# mini_backplane.net
KiCad netlist of a schematic drawn in Altium Designer
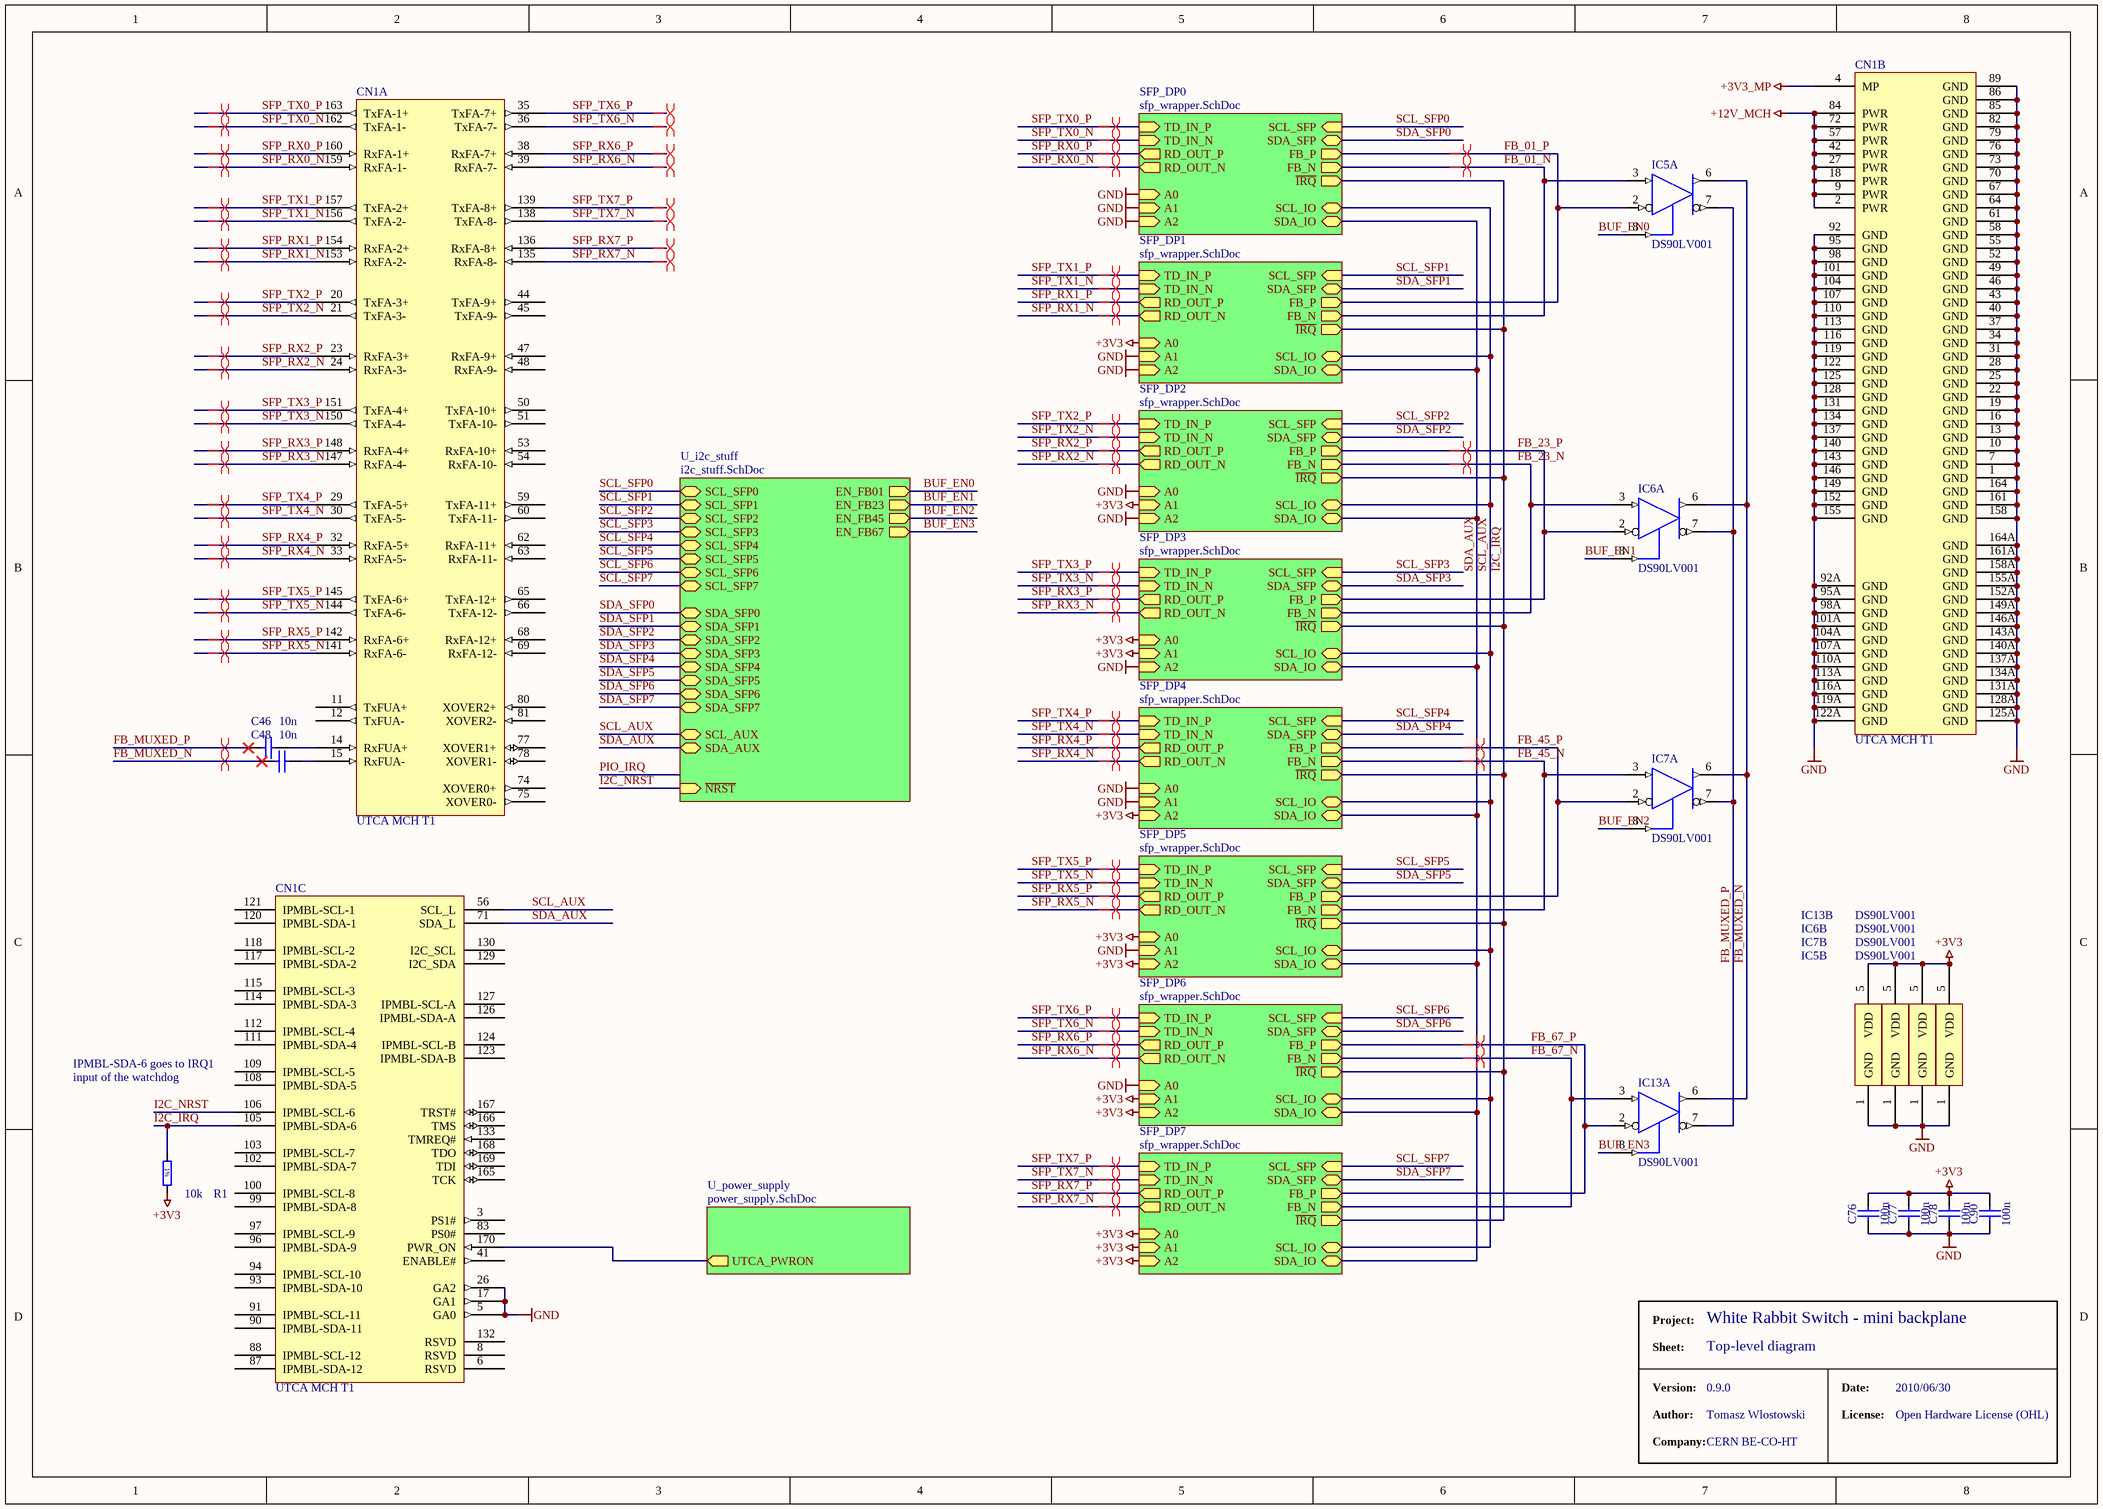
[diagram p0: mini_backplane.SchDoc]

(export (version "E")
  (design (tool "Eeschema 10.0.6"))
  (components
    (comp (ref "C46")
      (value "10n")
      (footprint "CAPC1608X87N")
      (description "Non-polarised capacitor")
      (fields
        (field (name "PART NUMBER") "CC0603_10NF_50V_10%_X7R")
        (field (name "VOLTAGE") "50V")
        (field (name "AUTHOR") "CERN DEM JLC")
      )
      (libsource (lib "Capacitors") (part "Capacitor - non polarized"))
    )
    (comp (ref "C48")
      (value "10n")
      (footprint "CAPC1608X87N")
      (description "Non-polarised capacitor")
      (fields
        (field (name "PART NUMBER") "CC0603_10NF_50V_10%_X7R")
        (field (name "VOLTAGE") "50V")
        (field (name "AUTHOR") "CERN DEM JLC")
      )
      (libsource (lib "Capacitors") (part "Capacitor - non polarized"))
    )
    (comp (ref "C76")
      (value "100n")
      (footprint "CAPC1608X87N")
      (description "Non-polarised capacitor")
      (fields
        (field (name "PART NUMBER") "CC0603_100NF_50V_10%_X7R")
        (field (name "VOLTAGE") "50V")
        (field (name "AUTHOR") "CERN DEM JLC")
      )
      (libsource (lib "Capacitors") (part "Capacitor - non polarized"))
    )
    (comp (ref "C77")
      (value "100n")
      (footprint "CAPC1608X87N")
      (description "Non-polarised capacitor")
      (fields
        (field (name "PART NUMBER") "CC0603_100NF_50V_10%_X7R")
        (field (name "VOLTAGE") "50V")
        (field (name "AUTHOR") "CERN DEM JLC")
      )
      (libsource (lib "Capacitors") (part "Capacitor - non polarized"))
    )
    (comp (ref "C78")
      (value "100n")
      (footprint "CAPC1608X87N")
      (description "Non-polarised capacitor")
      (fields
        (field (name "PART NUMBER") "CC0603_100NF_50V_10%_X7R")
        (field (name "VOLTAGE") "50V")
        (field (name "AUTHOR") "CERN DEM JLC")
      )
      (libsource (lib "Capacitors") (part "Capacitor - non polarized"))
    )
    (comp (ref "C90")
      (value "100n")
      (footprint "CAPC1608X87N")
      (description "Non-polarised capacitor")
      (fields
        (field (name "PART NUMBER") "CC0603_100NF_50V_10%_X7R")
        (field (name "VOLTAGE") "50V")
        (field (name "AUTHOR") "CERN DEM JLC")
      )
      (libsource (lib "Capacitors") (part "Capacitor - non polarized"))
    )
    (comp (ref "CN1")
      (value "UTCA MCH T1")
      (footprint "CON_AMC_MOLEX_75800_00001_REVERSE")
      (description "microTCA MTCA.0  MCH socket (AMC0.0 B+ connector with reversed pins)")
      (libsource (lib "wr_switch") (part "UTCA_MCH_SOCKET"))
    )
    (comp (ref "IC5")
      (value "DS90LV001")
      (footprint "SOIC127P600-8AL")
      (description "LVDS buffer with enable")
      (libsource (lib "wr_switch") (part "DS90LV001"))
    )
    (comp (ref "IC6")
      (value "DS90LV001")
      (footprint "SOIC127P600-8AL")
      (description "LVDS buffer with enable")
      (libsource (lib "wr_switch") (part "DS90LV001"))
    )
    (comp (ref "IC7")
      (value "DS90LV001")
      (footprint "SOIC127P600-8AL")
      (description "LVDS buffer with enable")
      (libsource (lib "wr_switch") (part "DS90LV001"))
    )
    (comp (ref "IC13")
      (value "DS90LV001")
      (footprint "SOIC127P600-8AL")
      (description "LVDS buffer with enable")
      (libsource (lib "wr_switch") (part "DS90LV001"))
    )
    (comp (ref "R1")
      (value "10k")
      (footprint "RESC1608X55N")
      (description "Resistor - 1%")
      (fields
        (field (name "PART NUMBER") "R0603_10K_1%_0.1W_100PPM")
        (field (name "POWER") "0.1W")
        (field (name "AUTHOR") "CERN DEM JLC")
      )
      (libsource (lib "Resistors") (part "Resistor - 1%"))
    )
  )
  (nets
    (net (code "1") (name "+3V3") (class "Default")
      (node (ref "C76") (pin "2") (pinfunction "2_2") (pintype "passive"))
      (node (ref "C77") (pin "2") (pinfunction "2_2") (pintype "passive"))
      (node (ref "C78") (pin "2") (pinfunction "2_2") (pintype "passive"))
      (node (ref "C90") (pin "2") (pinfunction "2_2") (pintype "passive"))
      (node (ref "IC13") (pin "5") (pinfunction "VDD_5") (pintype "power_in"))
      (node (ref "IC5") (pin "5") (pinfunction "VDD_5") (pintype "power_in"))
      (node (ref "IC6") (pin "5") (pinfunction "VDD_5") (pintype "power_in"))
      (node (ref "IC7") (pin "5") (pinfunction "VDD_5") (pintype "power_in"))
      (node (ref "R1") (pin "2") (pinfunction "2_2") (pintype "passive"))
    )
    (net (code "2") (name "+3V3_MP") (class "Default")
      (node (ref "CN1") (pin "4") (pinfunction "MP_4") (pintype "power_in"))
    )
    (net (code "3") (name "+12V_MCH") (class "Default")
      (node (ref "CN1") (pin "18") (pinfunction "PWR_18") (pintype "power_in"))
      (node (ref "CN1") (pin "2") (pinfunction "PWR_2") (pintype "power_in"))
      (node (ref "CN1") (pin "27") (pinfunction "PWR_27") (pintype "power_in"))
      (node (ref "CN1") (pin "42") (pinfunction "PWR_42") (pintype "power_in"))
      (node (ref "CN1") (pin "57") (pinfunction "PWR_57") (pintype "power_in"))
      (node (ref "CN1") (pin "72") (pinfunction "PWR_72") (pintype "power_in"))
      (node (ref "CN1") (pin "84") (pinfunction "PWR_84") (pintype "power_in"))
      (node (ref "CN1") (pin "9") (pinfunction "PWR_9") (pintype "power_in"))
    )
    (net (code "4") (name "/BUF_EN0") (class "Default")
      (node (ref "IC5") (pin "8") (pinfunction "EN_8") (pintype "input"))
    )
    (net (code "5") (name "/BUF_EN1") (class "Default")
      (node (ref "IC6") (pin "8") (pinfunction "EN_8") (pintype "input"))
    )
    (net (code "6") (name "/BUF_EN2") (class "Default")
      (node (ref "IC7") (pin "8") (pinfunction "EN_8") (pintype "input"))
    )
    (net (code "7") (name "/BUF_EN3") (class "Default")
      (node (ref "IC13") (pin "8") (pinfunction "EN_8") (pintype "input"))
    )
    (net (code "8") (name "/FB_01_N") (class "Default")
      (node (ref "IC5") (pin "3") (pinfunction "IN+_3") (pintype "input"))
    )
    (net (code "9") (name "/FB_01_P") (class "Default")
      (node (ref "IC5") (pin "2") (pinfunction "IN-_2") (pintype "input"))
    )
    (net (code "10") (name "/FB_23_N") (class "Default")
      (node (ref "IC6") (pin "3") (pinfunction "IN+_3") (pintype "input"))
    )
    (net (code "11") (name "/FB_23_P") (class "Default")
      (node (ref "IC6") (pin "2") (pinfunction "IN-_2") (pintype "input"))
    )
    (net (code "12") (name "/FB_45_N") (class "Default")
      (node (ref "IC7") (pin "3") (pinfunction "IN+_3") (pintype "input"))
    )
    (net (code "13") (name "/FB_45_P") (class "Default")
      (node (ref "IC7") (pin "2") (pinfunction "IN-_2") (pintype "input"))
    )
    (net (code "14") (name "/FB_67_N") (class "Default")
      (node (ref "IC13") (pin "3") (pinfunction "IN+_3") (pintype "input"))
    )
    (net (code "15") (name "/FB_67_P") (class "Default")
      (node (ref "IC13") (pin "2") (pinfunction "IN-_2") (pintype "input"))
    )
    (net (code "16") (name "/FB_MUXED_N") (class "Default")
      (node (ref "C48") (pin "1") (pinfunction "1_1") (pintype "passive"))
      (node (ref "IC13") (pin "6") (pinfunction "OUT+_6") (pintype "output"))
      (node (ref "IC5") (pin "6") (pinfunction "OUT+_6") (pintype "output"))
      (node (ref "IC6") (pin "6") (pinfunction "OUT+_6") (pintype "output"))
      (node (ref "IC7") (pin "6") (pinfunction "OUT+_6") (pintype "output"))
    )
    (net (code "17") (name "/FB_MUXED_P") (class "Default")
      (node (ref "C46") (pin "1") (pinfunction "1_1") (pintype "passive"))
      (node (ref "IC13") (pin "7") (pinfunction "OUT-_7") (pintype "output"))
      (node (ref "IC5") (pin "7") (pinfunction "OUT-_7") (pintype "output"))
      (node (ref "IC6") (pin "7") (pinfunction "OUT-_7") (pintype "output"))
      (node (ref "IC7") (pin "7") (pinfunction "OUT-_7") (pintype "output"))
    )
    (net (code "18") (name "/I2C_IRQ") (class "Default")
      (node (ref "CN1") (pin "105") (pinfunction "IPMBL-SDA-6_105") (pintype "open_collector"))
      (node (ref "R1") (pin "1") (pinfunction "1_1") (pintype "passive"))
    )
    (net (code "19") (name "/I2C_NRST") (class "Default")
      (node (ref "CN1") (pin "106") (pinfunction "IPMBL-SCL-6_106") (pintype "open_collector"))
    )
    (net (code "21") (name "/SCL_AUX") (class "Default")
      (node (ref "CN1") (pin "56") (pinfunction "SCL_L_56") (pintype "open_collector"))
    )
    (net (code "30") (name "/SDA_AUX") (class "Default")
      (node (ref "CN1") (pin "71") (pinfunction "SDA_L_71") (pintype "open_collector"))
    )
    (net (code "39") (name "/SFP_RX0_N") (class "Default")
      (node (ref "CN1") (pin "159") (pinfunction "RxFA-1-_159") (pintype "input"))
    )
    (net (code "40") (name "/SFP_RX0_P") (class "Default")
      (node (ref "CN1") (pin "160") (pinfunction "RxFA-1+_160") (pintype "input"))
    )
    (net (code "41") (name "/SFP_RX1_N") (class "Default")
      (node (ref "CN1") (pin "153") (pinfunction "RxFA-2-_153") (pintype "input"))
    )
    (net (code "42") (name "/SFP_RX1_P") (class "Default")
      (node (ref "CN1") (pin "154") (pinfunction "RxFA-2+_154") (pintype "input"))
    )
    (net (code "43") (name "/SFP_RX2_N") (class "Default")
      (node (ref "CN1") (pin "24") (pinfunction "RxFA-3-_24") (pintype "input"))
    )
    (net (code "44") (name "/SFP_RX2_P") (class "Default")
      (node (ref "CN1") (pin "23") (pinfunction "RxFA-3+_23") (pintype "input"))
    )
    (net (code "45") (name "/SFP_RX3_N") (class "Default")
      (node (ref "CN1") (pin "147") (pinfunction "RxFA-4-_147") (pintype "input"))
    )
    (net (code "46") (name "/SFP_RX3_P") (class "Default")
      (node (ref "CN1") (pin "148") (pinfunction "RxFA-4+_148") (pintype "input"))
    )
    (net (code "47") (name "/SFP_RX4_N") (class "Default")
      (node (ref "CN1") (pin "33") (pinfunction "RxFA-5-_33") (pintype "input"))
    )
    (net (code "48") (name "/SFP_RX4_P") (class "Default")
      (node (ref "CN1") (pin "32") (pinfunction "RxFA-5+_32") (pintype "input"))
    )
    (net (code "49") (name "/SFP_RX5_N") (class "Default")
      (node (ref "CN1") (pin "141") (pinfunction "RxFA-6-_141") (pintype "input"))
    )
    (net (code "50") (name "/SFP_RX5_P") (class "Default")
      (node (ref "CN1") (pin "142") (pinfunction "RxFA-6+_142") (pintype "input"))
    )
    (net (code "51") (name "/SFP_RX6_N") (class "Default")
      (node (ref "CN1") (pin "39") (pinfunction "RxFA-7-_39") (pintype "input"))
    )
    (net (code "52") (name "/SFP_RX6_P") (class "Default")
      (node (ref "CN1") (pin "38") (pinfunction "RxFA-7+_38") (pintype "input"))
    )
    (net (code "53") (name "/SFP_RX7_N") (class "Default")
      (node (ref "CN1") (pin "135") (pinfunction "RxFA-8-_135") (pintype "input"))
    )
    (net (code "54") (name "/SFP_RX7_P") (class "Default")
      (node (ref "CN1") (pin "136") (pinfunction "RxFA-8+_136") (pintype "input"))
    )
    (net (code "55") (name "/SFP_TX0_N") (class "Default")
      (node (ref "CN1") (pin "162") (pinfunction "TxFA-1-_162") (pintype "output"))
    )
    (net (code "56") (name "/SFP_TX0_P") (class "Default")
      (node (ref "CN1") (pin "163") (pinfunction "TxFA-1+_163") (pintype "output"))
    )
    (net (code "57") (name "/SFP_TX1_N") (class "Default")
      (node (ref "CN1") (pin "156") (pinfunction "TxFA-2-_156") (pintype "output"))
    )
    (net (code "58") (name "/SFP_TX1_P") (class "Default")
      (node (ref "CN1") (pin "157") (pinfunction "TxFA-2+_157") (pintype "output"))
    )
    (net (code "59") (name "/SFP_TX2_N") (class "Default")
      (node (ref "CN1") (pin "21") (pinfunction "TxFA-3-_21") (pintype "output"))
    )
    (net (code "60") (name "/SFP_TX2_P") (class "Default")
      (node (ref "CN1") (pin "20") (pinfunction "TxFA-3+_20") (pintype "output"))
    )
    (net (code "61") (name "/SFP_TX3_N") (class "Default")
      (node (ref "CN1") (pin "150") (pinfunction "TxFA-4-_150") (pintype "output"))
    )
    (net (code "62") (name "/SFP_TX3_P") (class "Default")
      (node (ref "CN1") (pin "151") (pinfunction "TxFA-4+_151") (pintype "output"))
    )
    (net (code "63") (name "/SFP_TX4_N") (class "Default")
      (node (ref "CN1") (pin "30") (pinfunction "TxFA-5-_30") (pintype "output"))
    )
    (net (code "64") (name "/SFP_TX4_P") (class "Default")
      (node (ref "CN1") (pin "29") (pinfunction "TxFA-5+_29") (pintype "output"))
    )
    (net (code "65") (name "/SFP_TX5_N") (class "Default")
      (node (ref "CN1") (pin "144") (pinfunction "TxFA-6-_144") (pintype "output"))
    )
    (net (code "66") (name "/SFP_TX5_P") (class "Default")
      (node (ref "CN1") (pin "145") (pinfunction "TxFA-6+_145") (pintype "output"))
    )
    (net (code "67") (name "/SFP_TX6_N") (class "Default")
      (node (ref "CN1") (pin "36") (pinfunction "TxFA-7-_36") (pintype "output"))
    )
    (net (code "68") (name "/SFP_TX6_P") (class "Default")
      (node (ref "CN1") (pin "35") (pinfunction "TxFA-7+_35") (pintype "output"))
    )
    (net (code "69") (name "/SFP_TX7_N") (class "Default")
      (node (ref "CN1") (pin "138") (pinfunction "TxFA-8-_138") (pintype "output"))
    )
    (net (code "70") (name "/SFP_TX7_P") (class "Default")
      (node (ref "CN1") (pin "139") (pinfunction "TxFA-8+_139") (pintype "output"))
    )
    (net (code "71") (name "/UTCA_PWRON") (class "Default")
      (node (ref "CN1") (pin "170") (pinfunction "PWR_ON_170") (pintype "input"))
    )
    (net (code "72") (name "GND") (class "Default")
      (node (ref "C76") (pin "1") (pinfunction "1_1") (pintype "passive"))
      (node (ref "C77") (pin "1") (pinfunction "1_1") (pintype "passive"))
      (node (ref "C78") (pin "1") (pinfunction "1_1") (pintype "passive"))
      (node (ref "C90") (pin "1") (pinfunction "1_1") (pintype "passive"))
      (node (ref "CN1") (pin "1") (pinfunction "GND_1") (pintype "power_in"))
      (node (ref "CN1") (pin "10") (pinfunction "GND_10") (pintype "power_in"))
      (node (ref "CN1") (pin "101") (pinfunction "GND_101") (pintype "power_in"))
      (node (ref "CN1") (pin "101A") (pinfunction "GND_101A") (pintype "power_in"))
      (node (ref "CN1") (pin "104") (pinfunction "GND_104") (pintype "power_in"))
      (node (ref "CN1") (pin "104A") (pinfunction "GND_104A") (pintype "power_in"))
      (node (ref "CN1") (pin "107") (pinfunction "GND_107") (pintype "power_in"))
      (node (ref "CN1") (pin "107A") (pinfunction "GND_107A") (pintype "power_in"))
      (node (ref "CN1") (pin "110") (pinfunction "GND_110") (pintype "power_in"))
      (node (ref "CN1") (pin "110A") (pinfunction "GND_110A") (pintype "power_in"))
      (node (ref "CN1") (pin "113") (pinfunction "GND_113") (pintype "power_in"))
      (node (ref "CN1") (pin "113A") (pinfunction "GND_113A") (pintype "power_in"))
      (node (ref "CN1") (pin "116") (pinfunction "GND_116") (pintype "power_in"))
      (node (ref "CN1") (pin "116A") (pinfunction "GND_116A") (pintype "power_in"))
      (node (ref "CN1") (pin "119") (pinfunction "GND_119") (pintype "power_in"))
      (node (ref "CN1") (pin "119A") (pinfunction "GND_119A") (pintype "power_in"))
      (node (ref "CN1") (pin "122") (pinfunction "GND_122") (pintype "power_in"))
      (node (ref "CN1") (pin "122A") (pinfunction "GND_122A") (pintype "power_in"))
      (node (ref "CN1") (pin "125") (pinfunction "GND_125") (pintype "power_in"))
      (node (ref "CN1") (pin "125A") (pinfunction "GND_125A") (pintype "power_in"))
      (node (ref "CN1") (pin "128") (pinfunction "GND_128") (pintype "power_in"))
      (node (ref "CN1") (pin "128A") (pinfunction "GND_128A") (pintype "power_in"))
      (node (ref "CN1") (pin "13") (pinfunction "GND_13") (pintype "power_in"))
      (node (ref "CN1") (pin "131") (pinfunction "GND_131") (pintype "power_in"))
      (node (ref "CN1") (pin "131A") (pinfunction "GND_131A") (pintype "power_in"))
      (node (ref "CN1") (pin "134") (pinfunction "GND_134") (pintype "power_in"))
      (node (ref "CN1") (pin "134A") (pinfunction "GND_134A") (pintype "power_in"))
      (node (ref "CN1") (pin "137") (pinfunction "GND_137") (pintype "power_in"))
      (node (ref "CN1") (pin "137A") (pinfunction "GND_137A") (pintype "power_in"))
      (node (ref "CN1") (pin "140") (pinfunction "GND_140") (pintype "power_in"))
      (node (ref "CN1") (pin "140A") (pinfunction "GND_140A") (pintype "power_in"))
      (node (ref "CN1") (pin "143") (pinfunction "GND_143") (pintype "power_in"))
      (node (ref "CN1") (pin "143A") (pinfunction "GND_143A") (pintype "power_in"))
      (node (ref "CN1") (pin "146") (pinfunction "GND_146") (pintype "power_in"))
      (node (ref "CN1") (pin "146A") (pinfunction "GND_146A") (pintype "power_in"))
      (node (ref "CN1") (pin "149") (pinfunction "GND_149") (pintype "power_in"))
      (node (ref "CN1") (pin "149A") (pinfunction "GND_149A") (pintype "power_in"))
      (node (ref "CN1") (pin "152") (pinfunction "GND_152") (pintype "power_in"))
      (node (ref "CN1") (pin "152A") (pinfunction "GND_152A") (pintype "power_in"))
      (node (ref "CN1") (pin "155") (pinfunction "GND_155") (pintype "power_in"))
      (node (ref "CN1") (pin "155A") (pinfunction "GND_155A") (pintype "power_in"))
      (node (ref "CN1") (pin "158") (pinfunction "GND_158") (pintype "power_in"))
      (node (ref "CN1") (pin "158A") (pinfunction "GND_158A") (pintype "power_in"))
      (node (ref "CN1") (pin "16") (pinfunction "GND_16") (pintype "power_in"))
      (node (ref "CN1") (pin "161") (pinfunction "GND_161") (pintype "power_in"))
      (node (ref "CN1") (pin "161A") (pinfunction "GND_161A") (pintype "power_in"))
      (node (ref "CN1") (pin "164") (pinfunction "GND_164") (pintype "power_in"))
      (node (ref "CN1") (pin "164A") (pinfunction "GND_164A") (pintype "power_in"))
      (node (ref "CN1") (pin "17") (pinfunction "GA1_17") (pintype "output"))
      (node (ref "CN1") (pin "19") (pinfunction "GND_19") (pintype "power_in"))
      (node (ref "CN1") (pin "22") (pinfunction "GND_22") (pintype "power_in"))
      (node (ref "CN1") (pin "25") (pinfunction "GND_25") (pintype "power_in"))
      (node (ref "CN1") (pin "26") (pinfunction "GA2_26") (pintype "output"))
      (node (ref "CN1") (pin "28") (pinfunction "GND_28") (pintype "power_in"))
      (node (ref "CN1") (pin "31") (pinfunction "GND_31") (pintype "power_in"))
      (node (ref "CN1") (pin "34") (pinfunction "GND_34") (pintype "power_in"))
      (node (ref "CN1") (pin "37") (pinfunction "GND_37") (pintype "power_in"))
      (node (ref "CN1") (pin "40") (pinfunction "GND_40") (pintype "power_in"))
      (node (ref "CN1") (pin "43") (pinfunction "GND_43") (pintype "power_in"))
      (node (ref "CN1") (pin "46") (pinfunction "GND_46") (pintype "power_in"))
      (node (ref "CN1") (pin "49") (pinfunction "GND_49") (pintype "power_in"))
      (node (ref "CN1") (pin "5") (pinfunction "GA0_5") (pintype "output"))
      (node (ref "CN1") (pin "52") (pinfunction "GND_52") (pintype "power_in"))
      (node (ref "CN1") (pin "55") (pinfunction "GND_55") (pintype "power_in"))
      (node (ref "CN1") (pin "58") (pinfunction "GND_58") (pintype "power_in"))
      (node (ref "CN1") (pin "61") (pinfunction "GND_61") (pintype "power_in"))
      (node (ref "CN1") (pin "64") (pinfunction "GND_64") (pintype "power_in"))
      (node (ref "CN1") (pin "67") (pinfunction "GND_67") (pintype "power_in"))
      (node (ref "CN1") (pin "7") (pinfunction "GND_7") (pintype "power_in"))
      (node (ref "CN1") (pin "70") (pinfunction "GND_70") (pintype "power_in"))
      (node (ref "CN1") (pin "73") (pinfunction "GND_73") (pintype "power_in"))
      (node (ref "CN1") (pin "76") (pinfunction "GND_76") (pintype "power_in"))
      (node (ref "CN1") (pin "79") (pinfunction "GND_79") (pintype "power_in"))
      (node (ref "CN1") (pin "82") (pinfunction "GND_82") (pintype "power_in"))
      (node (ref "CN1") (pin "85") (pinfunction "GND_85") (pintype "power_in"))
      (node (ref "CN1") (pin "86") (pinfunction "GND_86") (pintype "power_in"))
      (node (ref "CN1") (pin "89") (pinfunction "GND_89") (pintype "power_in"))
      (node (ref "CN1") (pin "92") (pinfunction "GND_92") (pintype "power_in"))
      (node (ref "CN1") (pin "92A") (pinfunction "GND_92A") (pintype "power_in"))
      (node (ref "CN1") (pin "95") (pinfunction "GND_95") (pintype "power_in"))
      (node (ref "CN1") (pin "95A") (pinfunction "GND_95A") (pintype "power_in"))
      (node (ref "CN1") (pin "98") (pinfunction "GND_98") (pintype "power_in"))
      (node (ref "CN1") (pin "98A") (pinfunction "GND_98A") (pintype "power_in"))
      (node (ref "IC13") (pin "1") (pinfunction "GND_1") (pintype "power_in"))
      (node (ref "IC5") (pin "1") (pinfunction "GND_1") (pintype "power_in"))
      (node (ref "IC6") (pin "1") (pinfunction "GND_1") (pintype "power_in"))
      (node (ref "IC7") (pin "1") (pinfunction "GND_1") (pintype "power_in"))
    )
    (net (code "73") (name "Net-(CN1A-RxFUA+)") (class "Default")
      (node (ref "C46") (pin "2") (pinfunction "2_2") (pintype "passive"))
      (node (ref "CN1") (pin "14") (pinfunction "RxFUA+_14") (pintype "input"))
    )
    (net (code "74") (name "Net-(CN1A-RxFUA-)") (class "Default")
      (node (ref "C48") (pin "2") (pinfunction "2_2") (pintype "passive"))
      (node (ref "CN1") (pin "15") (pinfunction "RxFUA-_15") (pintype "input"))
    )
    (net (code "75") (name "unconnected-(CN1A-RxFA-9+-Pad47)") (class "Default")
      (node (ref "CN1") (pin "47") (pinfunction "RxFA-9+_47") (pintype "input"))
    )
    (net (code "76") (name "unconnected-(CN1A-RxFA-9--Pad48)") (class "Default")
      (node (ref "CN1") (pin "48") (pinfunction "RxFA-9-_48") (pintype "input"))
    )
    (net (code "77") (name "unconnected-(CN1A-RxFA-10+-Pad53)") (class "Default")
      (node (ref "CN1") (pin "53") (pinfunction "RxFA-10+_53") (pintype "input"))
    )
    (net (code "78") (name "unconnected-(CN1A-RxFA-10--Pad54)") (class "Default")
      (node (ref "CN1") (pin "54") (pinfunction "RxFA-10-_54") (pintype "input"))
    )
    (net (code "79") (name "unconnected-(CN1A-RxFA-11+-Pad62)") (class "Default")
      (node (ref "CN1") (pin "62") (pinfunction "RxFA-11+_62") (pintype "input"))
    )
    (net (code "80") (name "unconnected-(CN1A-RxFA-11--Pad63)") (class "Default")
      (node (ref "CN1") (pin "63") (pinfunction "RxFA-11-_63") (pintype "input"))
    )
    (net (code "81") (name "unconnected-(CN1A-RxFA-12+-Pad68)") (class "Default")
      (node (ref "CN1") (pin "68") (pinfunction "RxFA-12+_68") (pintype "input"))
    )
    (net (code "82") (name "unconnected-(CN1A-RxFA-12--Pad69)") (class "Default")
      (node (ref "CN1") (pin "69") (pinfunction "RxFA-12-_69") (pintype "input"))
    )
    (net (code "83") (name "unconnected-(CN1A-TxFA-9+-Pad44)") (class "Default")
      (node (ref "CN1") (pin "44") (pinfunction "TxFA-9+_44") (pintype "output"))
    )
    (net (code "84") (name "unconnected-(CN1A-TxFA-9--Pad45)") (class "Default")
      (node (ref "CN1") (pin "45") (pinfunction "TxFA-9-_45") (pintype "output"))
    )
    (net (code "85") (name "unconnected-(CN1A-TxFA-10+-Pad50)") (class "Default")
      (node (ref "CN1") (pin "50") (pinfunction "TxFA-10+_50") (pintype "output"))
    )
    (net (code "86") (name "unconnected-(CN1A-TxFA-10--Pad51)") (class "Default")
      (node (ref "CN1") (pin "51") (pinfunction "TxFA-10-_51") (pintype "output"))
    )
    (net (code "87") (name "unconnected-(CN1A-TxFA-11+-Pad59)") (class "Default")
      (node (ref "CN1") (pin "59") (pinfunction "TxFA-11+_59") (pintype "output"))
    )
    (net (code "88") (name "unconnected-(CN1A-TxFA-11--Pad60)") (class "Default")
      (node (ref "CN1") (pin "60") (pinfunction "TxFA-11-_60") (pintype "output"))
    )
    (net (code "89") (name "unconnected-(CN1A-TxFA-12+-Pad65)") (class "Default")
      (node (ref "CN1") (pin "65") (pinfunction "TxFA-12+_65") (pintype "output"))
    )
    (net (code "90") (name "unconnected-(CN1A-TxFA-12--Pad66)") (class "Default")
      (node (ref "CN1") (pin "66") (pinfunction "TxFA-12-_66") (pintype "output"))
    )
    (net (code "91") (name "unconnected-(CN1A-TxFUA+-Pad11)") (class "Default")
      (node (ref "CN1") (pin "11") (pinfunction "TxFUA+_11") (pintype "output"))
    )
    (net (code "92") (name "unconnected-(CN1A-TxFUA--Pad12)") (class "Default")
      (node (ref "CN1") (pin "12") (pinfunction "TxFUA-_12") (pintype "output"))
    )
    (net (code "93") (name "unconnected-(CN1A-XOVER0+-Pad74)") (class "Default")
      (node (ref "CN1") (pin "74") (pinfunction "XOVER0+_74") (pintype "output"))
    )
    (net (code "94") (name "unconnected-(CN1A-XOVER0--Pad75)") (class "Default")
      (node (ref "CN1") (pin "75") (pinfunction "XOVER0-_75") (pintype "output"))
    )
    (net (code "95") (name "unconnected-(CN1A-XOVER1+-Pad77)") (class "Default")
      (node (ref "CN1") (pin "77") (pinfunction "XOVER1+_77") (pintype "bidirectional"))
    )
    (net (code "96") (name "unconnected-(CN1A-XOVER1--Pad78)") (class "Default")
      (node (ref "CN1") (pin "78") (pinfunction "XOVER1-_78") (pintype "bidirectional"))
    )
    (net (code "97") (name "unconnected-(CN1A-XOVER2+-Pad80)") (class "Default")
      (node (ref "CN1") (pin "80") (pinfunction "XOVER2+_80") (pintype "input"))
    )
    (net (code "98") (name "unconnected-(CN1A-XOVER2--Pad81)") (class "Default")
      (node (ref "CN1") (pin "81") (pinfunction "XOVER2-_81") (pintype "input"))
    )
    (net (code "99") (name "unconnected-(CN1C-ENABLE#-Pad41)") (class "Default")
      (node (ref "CN1") (pin "41") (pinfunction "ENABLE#_41") (pintype "output"))
    )
    (net (code "100") (name "unconnected-(CN1C-I2C_SCL-Pad130)") (class "Default")
      (node (ref "CN1") (pin "130") (pinfunction "I2C_SCL_130") (pintype "open_collector"))
    )
    (net (code "101") (name "unconnected-(CN1C-I2C_SDA-Pad129)") (class "Default")
      (node (ref "CN1") (pin "129") (pinfunction "I2C_SDA_129") (pintype "open_collector"))
    )
    (net (code "102") (name "unconnected-(CN1C-IPMBL-SCL-1-Pad121)") (class "Default")
      (node (ref "CN1") (pin "121") (pinfunction "IPMBL-SCL-1_121") (pintype "open_collector"))
    )
    (net (code "103") (name "unconnected-(CN1C-IPMBL-SCL-2-Pad118)") (class "Default")
      (node (ref "CN1") (pin "118") (pinfunction "IPMBL-SCL-2_118") (pintype "open_collector"))
    )
    (net (code "104") (name "unconnected-(CN1C-IPMBL-SCL-3-Pad115)") (class "Default")
      (node (ref "CN1") (pin "115") (pinfunction "IPMBL-SCL-3_115") (pintype "open_collector"))
    )
    (net (code "105") (name "unconnected-(CN1C-IPMBL-SCL-4-Pad112)") (class "Default")
      (node (ref "CN1") (pin "112") (pinfunction "IPMBL-SCL-4_112") (pintype "open_collector"))
    )
    (net (code "106") (name "unconnected-(CN1C-IPMBL-SCL-5-Pad109)") (class "Default")
      (node (ref "CN1") (pin "109") (pinfunction "IPMBL-SCL-5_109") (pintype "open_collector"))
    )
    (net (code "107") (name "unconnected-(CN1C-IPMBL-SCL-7-Pad103)") (class "Default")
      (node (ref "CN1") (pin "103") (pinfunction "IPMBL-SCL-7_103") (pintype "open_collector"))
    )
    (net (code "108") (name "unconnected-(CN1C-IPMBL-SCL-8-Pad100)") (class "Default")
      (node (ref "CN1") (pin "100") (pinfunction "IPMBL-SCL-8_100") (pintype "open_collector"))
    )
    (net (code "109") (name "unconnected-(CN1C-IPMBL-SCL-9-Pad97)") (class "Default")
      (node (ref "CN1") (pin "97") (pinfunction "IPMBL-SCL-9_97") (pintype "open_collector"))
    )
    (net (code "110") (name "unconnected-(CN1C-IPMBL-SCL-10-Pad94)") (class "Default")
      (node (ref "CN1") (pin "94") (pinfunction "IPMBL-SCL-10_94") (pintype "open_collector"))
    )
    (net (code "111") (name "unconnected-(CN1C-IPMBL-SCL-11-Pad91)") (class "Default")
      (node (ref "CN1") (pin "91") (pinfunction "IPMBL-SCL-11_91") (pintype "open_collector"))
    )
    (net (code "112") (name "unconnected-(CN1C-IPMBL-SCL-12-Pad88)") (class "Default")
      (node (ref "CN1") (pin "88") (pinfunction "IPMBL-SCL-12_88") (pintype "open_collector"))
    )
    (net (code "113") (name "unconnected-(CN1C-IPMBL-SCL-A-Pad127)") (class "Default")
      (node (ref "CN1") (pin "127") (pinfunction "IPMBL-SCL-A_127") (pintype "open_collector"))
    )
    (net (code "114") (name "unconnected-(CN1C-IPMBL-SCL-B-Pad124)") (class "Default")
      (node (ref "CN1") (pin "124") (pinfunction "IPMBL-SCL-B_124") (pintype "open_collector"))
    )
    (net (code "115") (name "unconnected-(CN1C-IPMBL-SDA-1-Pad120)") (class "Default")
      (node (ref "CN1") (pin "120") (pinfunction "IPMBL-SDA-1_120") (pintype "open_collector"))
    )
    (net (code "116") (name "unconnected-(CN1C-IPMBL-SDA-2-Pad117)") (class "Default")
      (node (ref "CN1") (pin "117") (pinfunction "IPMBL-SDA-2_117") (pintype "open_collector"))
    )
    (net (code "117") (name "unconnected-(CN1C-IPMBL-SDA-3-Pad114)") (class "Default")
      (node (ref "CN1") (pin "114") (pinfunction "IPMBL-SDA-3_114") (pintype "open_collector"))
    )
    (net (code "118") (name "unconnected-(CN1C-IPMBL-SDA-4-Pad111)") (class "Default")
      (node (ref "CN1") (pin "111") (pinfunction "IPMBL-SDA-4_111") (pintype "open_collector"))
    )
    (net (code "119") (name "unconnected-(CN1C-IPMBL-SDA-5-Pad108)") (class "Default")
      (node (ref "CN1") (pin "108") (pinfunction "IPMBL-SDA-5_108") (pintype "open_collector"))
    )
    (net (code "120") (name "unconnected-(CN1C-IPMBL-SDA-7-Pad102)") (class "Default")
      (node (ref "CN1") (pin "102") (pinfunction "IPMBL-SDA-7_102") (pintype "open_collector"))
    )
    (net (code "121") (name "unconnected-(CN1C-IPMBL-SDA-8-Pad99)") (class "Default")
      (node (ref "CN1") (pin "99") (pinfunction "IPMBL-SDA-8_99") (pintype "open_collector"))
    )
    (net (code "122") (name "unconnected-(CN1C-IPMBL-SDA-9-Pad96)") (class "Default")
      (node (ref "CN1") (pin "96") (pinfunction "IPMBL-SDA-9_96") (pintype "open_collector"))
    )
    (net (code "123") (name "unconnected-(CN1C-IPMBL-SDA-10-Pad93)") (class "Default")
      (node (ref "CN1") (pin "93") (pinfunction "IPMBL-SDA-10_93") (pintype "open_collector"))
    )
    (net (code "124") (name "unconnected-(CN1C-IPMBL-SDA-11-Pad90)") (class "Default")
      (node (ref "CN1") (pin "90") (pinfunction "IPMBL-SDA-11_90") (pintype "open_collector"))
    )
    (net (code "125") (name "unconnected-(CN1C-IPMBL-SDA-12-Pad87)") (class "Default")
      (node (ref "CN1") (pin "87") (pinfunction "IPMBL-SDA-12_87") (pintype "open_collector"))
    )
    (net (code "126") (name "unconnected-(CN1C-IPMBL-SDA-A-Pad126)") (class "Default")
      (node (ref "CN1") (pin "126") (pinfunction "IPMBL-SDA-A_126") (pintype "open_collector"))
    )
    (net (code "127") (name "unconnected-(CN1C-IPMBL-SDA-B-Pad123)") (class "Default")
      (node (ref "CN1") (pin "123") (pinfunction "IPMBL-SDA-B_123") (pintype "open_collector"))
    )
    (net (code "128") (name "unconnected-(CN1C-PS0#-Pad83)") (class "Default")
      (node (ref "CN1") (pin "83") (pinfunction "PS0#_83") (pintype "passive"))
    )
    (net (code "129") (name "unconnected-(CN1C-PS1#-Pad3)") (class "Default")
      (node (ref "CN1") (pin "3") (pinfunction "PS1#_3") (pintype "output"))
    )
    (net (code "130") (name "unconnected-(CN1C-RSVD-Pad6)") (class "Default")
      (node (ref "CN1") (pin "6") (pinfunction "RSVD_6") (pintype "tri_state"))
    )
    (net (code "131") (name "unconnected-(CN1C-RSVD-Pad8)") (class "Default")
      (node (ref "CN1") (pin "8") (pinfunction "RSVD_8") (pintype "tri_state"))
    )
    (net (code "132") (name "unconnected-(CN1C-RSVD-Pad132)") (class "Default")
      (node (ref "CN1") (pin "132") (pinfunction "RSVD_132") (pintype "tri_state"))
    )
    (net (code "133") (name "unconnected-(CN1C-TCK-Pad165)") (class "Default")
      (node (ref "CN1") (pin "165") (pinfunction "TCK_165") (pintype "bidirectional"))
    )
    (net (code "134") (name "unconnected-(CN1C-TDI-Pad169)") (class "Default")
      (node (ref "CN1") (pin "169") (pinfunction "TDI_169") (pintype "bidirectional"))
    )
    (net (code "135") (name "unconnected-(CN1C-TDO-Pad168)") (class "Default")
      (node (ref "CN1") (pin "168") (pinfunction "TDO_168") (pintype "bidirectional"))
    )
    (net (code "136") (name "unconnected-(CN1C-TMREQ#-Pad133)") (class "Default")
      (node (ref "CN1") (pin "133") (pinfunction "TMREQ#_133") (pintype "input"))
    )
    (net (code "137") (name "unconnected-(CN1C-TMS-Pad166)") (class "Default")
      (node (ref "CN1") (pin "166") (pinfunction "TMS_166") (pintype "bidirectional"))
    )
    (net (code "138") (name "unconnected-(CN1C-TRST#-Pad167)") (class "Default")
      (node (ref "CN1") (pin "167") (pinfunction "TRST#_167") (pintype "bidirectional"))
    )
  )
)
